# PSU.net
KiCad netlist of a schematic drawn in Altium Designer
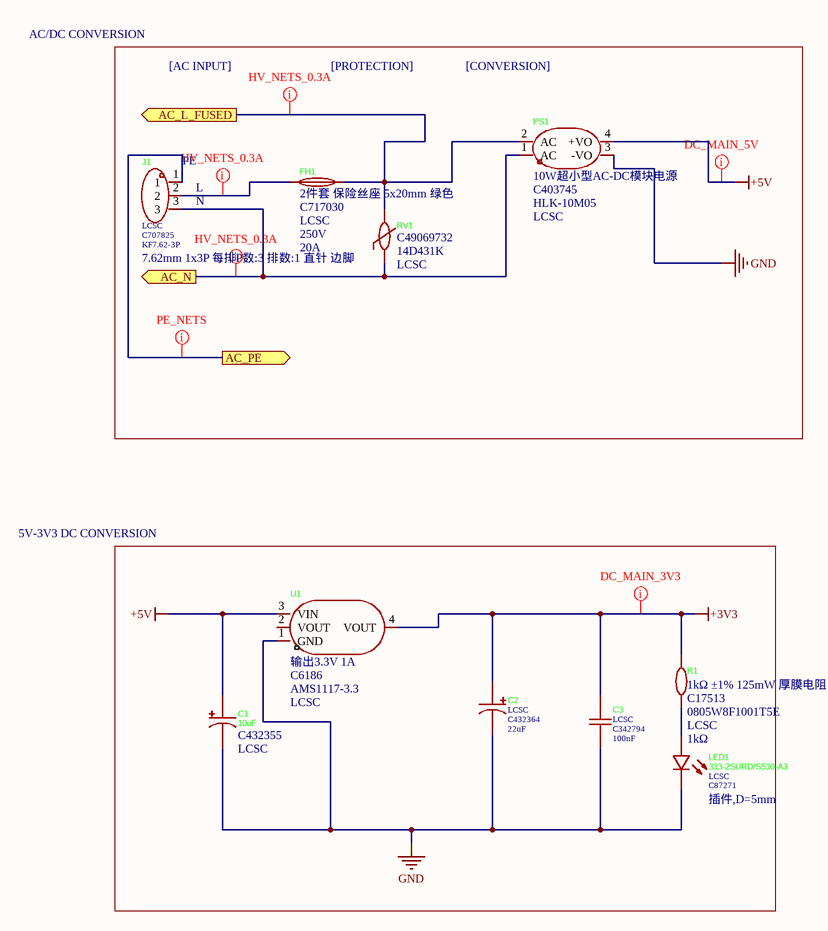
[diagram p0: PSU.SchDoc]

(export (version "E")
  (design (tool "Eeschema 10.0.6"))
  (components
    (comp (ref "C1")
      (value "10uF")
      (footprint "CAP-TH_BD5.0-P2.00-D0.8-FD:CAP-TH_BD5.0-P2.00-D0.8-FD")
      (fields
        (field (name "MANUFACTURER") "Rubycon(红宝石)")
        (field (name "MANUFACTURER PART") "50YXJ10M5X11")
        (field (name "TOLERANCE") "±20%")
        (field (name "SUPPLIER PART") "C432355")
        (field (name "SUPPLIER") "LCSC")
      )
      (libsource (lib "50YXJ10M5X111_50YXJ10M5X11") (part "50YXJ10M5X11"))
    )
    (comp (ref "C2")
      (value "22uF")
      (footprint "CAP-TH_BD5.0-P2.00-D0.5-FD-1:CAP-TH_BD5.0-P2.00-D0.5-FD-1")
      (fields
        (field (name "MANUFACTURER") "rubycon(红宝石)")
        (field (name "MANUFACTURER PART") "50YXJ22M5X11")
        (field (name "TOLERANCE") "±20%")
        (field (name "SUPPLIER") "LCSC")
        (field (name "SUPPLIER PART") "C432364")
      )
      (libsource (lib "50YXJ22M5X111_50YXJ22M5X11") (part "50YXJ22M5X11"))
    )
    (comp (ref "C3")
      (value "100nF")
      (footprint "CAP-TH_L4.0-W2.5-P5.00-D1.0:CAP-TH_L4.0-W2.5-P5.00-D1.0")
      (fields
        (field (name "MANUFACTURER") "TDK")
        (field (name "MANUFACTURER PART") "FG28X7R1H104KNT06")
        (field (name "TOLERANCE") "±10%")
        (field (name "SUPPLIER") "LCSC")
        (field (name "SUPPLIER PART") "C342794")
      )
      (libsource (lib "FG28X7R1H104KNT061_FG28X7R1H104KNT06") (part "FG28X7R1H104KNT06"))
    )
    (comp (ref "FH1")
      (value "PTF-77")
      (footprint "FUSE-TH_L24.4-W9.4-P22.60")
      (fields
        (field (name "MANUFACTURER") "XFCN(兴飞)")
        (field (name "LCSC PART NAME") "2件套 保险丝座 5x20mm 绿色")
        (field (name "SUPPLIER PART") "C717030")
        (field (name "SUPPLIER") "LCSC")
        (field (name "VOLTAGE RATING") "250V")
        (field (name "CURRENT RATING") "20A")
      )
      (libsource (lib "5x20_PTF_771_20A") (part "PTF-77"))
    )
    (comp (ref "J1")
      (value "KF7.62-3P")
      (footprint "CONN-TH_KF7.62-3P:CONN-TH_KF7.62-3P")
      (fields
        (field (name "MANUFACTURER") "KEFA(科发)")
        (field (name "SUPPLIER") "LCSC")
        (field (name "SUPPLIER PART") "C707825")
        (field (name "MANUFACTURER PART") "KF7.62-3P")
        (field (name "LCSC PART NAME") "7.62mm 1x3P 每排P数:3 排数:1 直针 边脚")
      )
      (libsource (lib "KF7.62-3P1_KF7.62-3P") (part "KF7.62-3P"))
    )
    (comp (ref "LED1")
      (value "333-2SURD/S530-A3")
      (footprint "LED-TH_BD5.9-P2.54-RD_RED:LED-TH_BD5.9-P2.54-RD_RED")
      (fields
        (field (name "MANUFACTURER") "EVERLIGHT(亿光)")
        (field (name "SUPPLIER") "LCSC")
        (field (name "SUPPLIER PART") "C87271")
        (field (name "SUPPLIER FOOTPRINT") "插件,D=5mm")
      )
      (libsource (lib "333-2SURD_S530-A31_333-2SURD_S530-A3") (part "333-2SURD/S530-A3"))
    )
    (comp (ref "PS1")
      (value "HLK-10M05")
      (footprint "PWRM-TH_HLK-10M05")
      (fields
        (field (name "MANUFACTURER") "HI-LINK(海凌科)")
        (field (name "LCSC PART NAME") "10W超小型AC-DC模块电源")
        (field (name "SUPPLIER PART") "C403745")
        (field (name "MANUFACTURER PART") "HLK-10M05")
        (field (name "SUPPLIER") "LCSC")
      )
      (libsource (lib "HLK-10M05") (part "HLK-10M05"))
    )
    (comp (ref "R1")
      (value "1kΩ")
      (footprint "R0805")
      (fields
        (field (name "MANUFACTURER") "UNI-ROYAL(厚声)")
        (field (name "TOLERANCE") "±1%")
        (field (name "LCSC PART NAME") "1kΩ ±1% 125mW 厚膜电阻")
        (field (name "SUPPLIER PART") "C17513")
        (field (name "MANUFACTURER PART") "0805W8F1001T5E")
        (field (name "SUPPLIER") "LCSC")
      )
      (libsource (lib "1k_0805W8F1001T5E1") (part "0805W8F1001T5E"))
    )
    (comp (ref "RV1")
      (value "440pF")
      (footprint "RES-TH_L14.5-W6.0-P7.50-D0.8-S6.0")
      (fields
        (field (name "MANUFACTURER") "R+O(宏嘉诚)")
        (field (name "SUPPLIER PART") "C49069732")
        (field (name "MANUFACTURER PART") "14D431K")
        (field (name "SUPPLIER") "LCSC")
      )
      (libsource (lib "14D431K") (part "14D431K_C49069732"))
    )
    (comp (ref "U1")
      (value "AMS1117-3.3")
      (footprint "SOT-223-3_L6.5-W3.4-P2.30-LS7.0-BR")
      (fields
        (field (name "MANUFACTURER") "AMS")
        (field (name "LCSC PART NAME") "输出3.3V 1A")
        (field (name "SUPPLIER PART") "C6186")
        (field (name "MANUFACTURER PART") "AMS1117-3.3")
        (field (name "SUPPLIER") "LCSC")
      )
      (libsource (lib "AMSS117-3_31") (part "AMS1117-3.3_C6186"))
    )
  )
  (nets
    (net (code "1") (name "+3V3") (class "Default")
      (node (ref "C2") (pin "1") (pinfunction "1_1") (pintype "passive"))
      (node (ref "C3") (pin "1") (pinfunction "1_1") (pintype "passive"))
      (node (ref "R1") (pin "2") (pinfunction "2_2") (pintype "passive"))
      (node (ref "U1") (pin "4") (pinfunction "VOUT_4") (pintype "passive"))
    )
    (net (code "2") (name "+5V") (class "Default")
      (node (ref "C1") (pin "1") (pinfunction "1_1") (pintype "passive"))
      (node (ref "PS1") (pin "4") (pinfunction "+VO_4") (pintype "passive"))
      (node (ref "U1") (pin "3") (pinfunction "VIN_3") (pintype "passive"))
    )
    (net (code "3") (name "/AC_L_FUSED") (class "Default")
      (node (ref "FH1") (pin "2") (pinfunction "2_2") (pintype "passive"))
      (node (ref "PS1") (pin "2") (pinfunction "AC_2") (pintype "passive"))
      (node (ref "RV1") (pin "2") (pinfunction "2_2") (pintype "passive"))
    )
    (net (code "4") (name "/AC_N") (class "Default")
      (node (ref "J1") (pin "3") (pinfunction "3_3") (pintype "passive"))
      (node (ref "PS1") (pin "1") (pinfunction "AC_1") (pintype "passive"))
      (node (ref "RV1") (pin "1") (pinfunction "1_1") (pintype "passive"))
    )
    (net (code "5") (name "/AC_PE") (class "Default")
      (node (ref "J1") (pin "1") (pinfunction "1_1") (pintype "passive"))
    )
    (net (code "6") (name "GND") (class "Default")
      (node (ref "C1") (pin "2") (pinfunction "2_2") (pintype "passive"))
      (node (ref "C2") (pin "2") (pinfunction "2_2") (pintype "passive"))
      (node (ref "C3") (pin "2") (pinfunction "2_2") (pintype "passive"))
      (node (ref "LED1") (pin "1") (pinfunction "C_1") (pintype "passive"))
      (node (ref "PS1") (pin "3") (pinfunction "-VO_3") (pintype "passive"))
      (node (ref "U1") (pin "1") (pinfunction "GND_1") (pintype "passive"))
    )
    (net (code "7") (name "Net-(FH1-Pad1)") (class "Default")
      (node (ref "FH1") (pin "1") (pinfunction "1_1") (pintype "passive"))
      (node (ref "J1") (pin "2") (pinfunction "2_2") (pintype "passive"))
    )
    (net (code "8") (name "Net-(LED1-A)") (class "Default")
      (node (ref "LED1") (pin "2") (pinfunction "A_2") (pintype "passive"))
      (node (ref "R1") (pin "1") (pinfunction "1_1") (pintype "passive"))
    )
    (net (code "9") (name "unconnected-(U1-VOUT-Pad2)") (class "Default")
      (node (ref "U1") (pin "2") (pinfunction "VOUT_2") (pintype "passive"))
    )
  )
)
